# Haar_Primal_HardMount.net
KiCad netlist of a schematic drawn in EAGLE
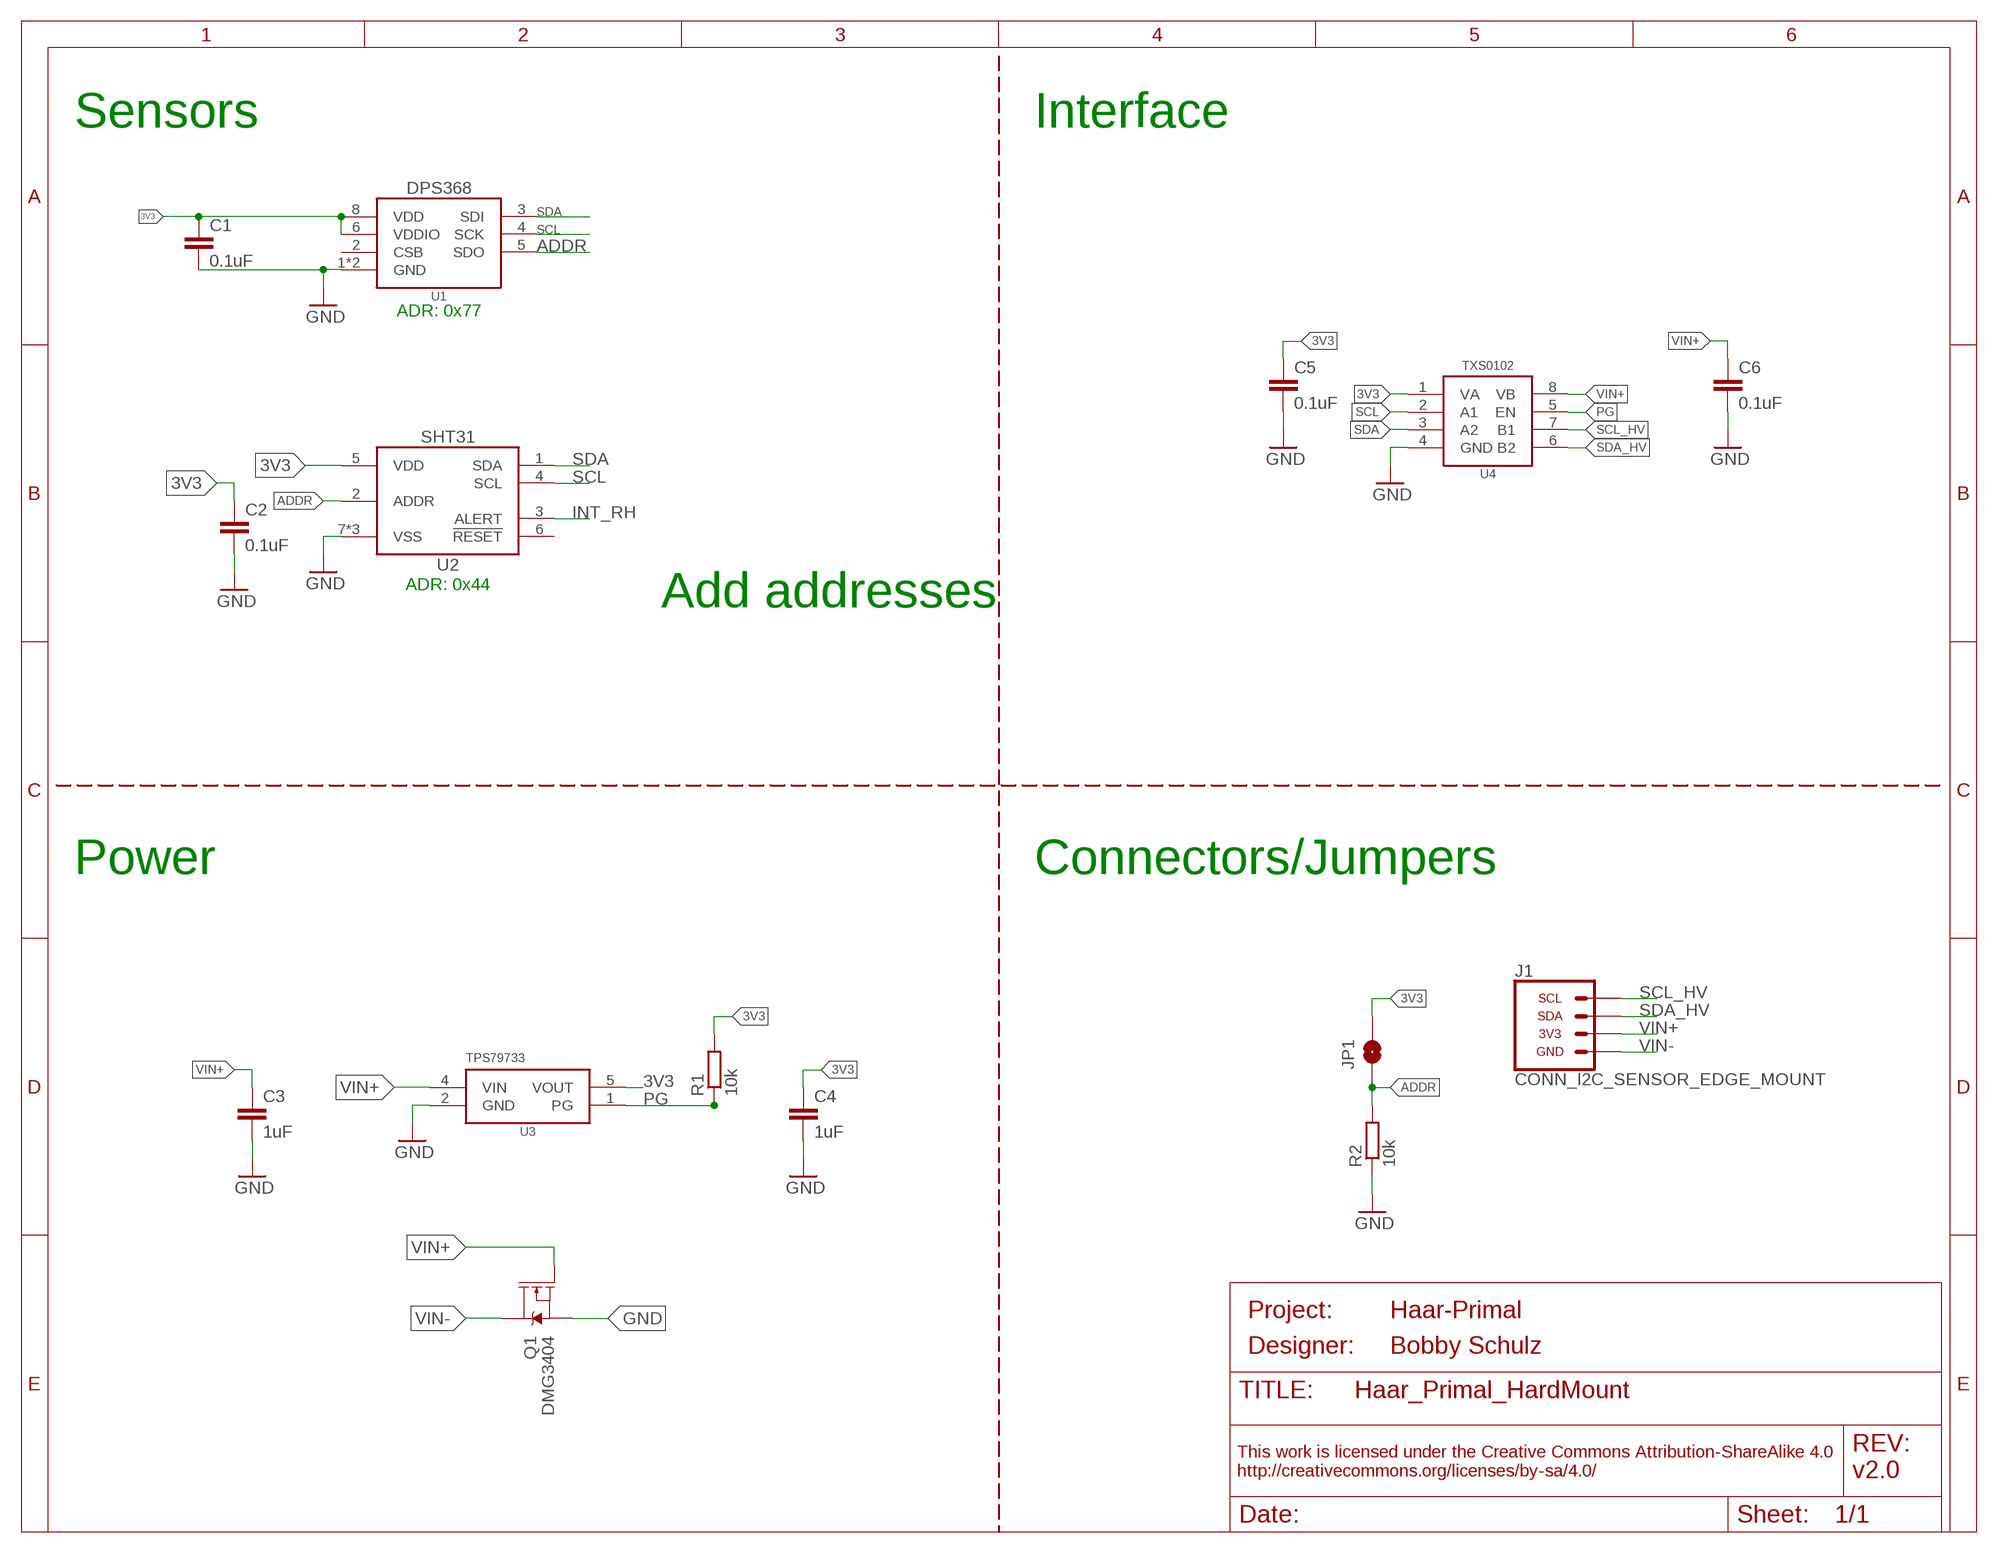
[diagram p0: schematic, sheet 1]

(export (version "E")
  (design (tool "Eeschema 10.0.6"))
  (components
    (comp (ref "C1")
      (value "0.1uF")
      (footprint "eagle-import:C0603")
      (fields (field (name "MF") "Murata") (field (name "MPN") "GCM188R71E104KA57D"))
      (libsource (lib "eagle-import") (part "C-EUC06030.1UF"))
    )
    (comp (ref "C2")
      (value "0.1uF")
      (footprint "eagle-import:C0603")
      (fields (field (name "MF") "Murata") (field (name "MPN") "GCM188R71E104KA57D"))
      (libsource (lib "eagle-import") (part "C-EUC06030.1UF"))
    )
    (comp (ref "C3")
      (value "1uF")
      (footprint "eagle-import:C0603")
      (fields (field (name "MF") "Yaiyo Yuden") (field (name "MPN") "EMK107BJ105KA-T"))
      (libsource (lib "eagle-import") (part "C-EUC06031UF"))
    )
    (comp (ref "C4")
      (value "1uF")
      (footprint "eagle-import:C0603")
      (fields (field (name "MF") "Yaiyo Yuden") (field (name "MPN") "EMK107BJ105KA-T"))
      (libsource (lib "eagle-import") (part "C-EUC06031UF"))
    )
    (comp (ref "C5")
      (value "0.1uF")
      (footprint "eagle-import:C0603")
      (fields (field (name "MF") "Murata") (field (name "MPN") "GCM188R71E104KA57D"))
      (libsource (lib "eagle-import") (part "C-EUC06030.1UF"))
    )
    (comp (ref "C6")
      (value "0.1uF")
      (footprint "eagle-import:C0603")
      (fields (field (name "MF") "Murata") (field (name "MPN") "GCM188R71E104KA57D"))
      (libsource (lib "eagle-import") (part "C-EUC06030.1UF"))
    )
    (comp (ref "J1")
      (value "CONN_I2C_SENSOR_EDGE_MOUNT")
      (footprint "eagle-import:SOLDERCUP_CONN_QUAD")
      (fields (field (name "MF") "TE Connectivity") (field (name "MPN") "1838893-2"))
      (libsource (lib "eagle-import") (part "CONN_I2C_SENSOR_EDGE_MOUNT"))
    )
    (comp (ref "JP1")
      (value "JUMPER-SMT_2_NO_SILK")
      (footprint "eagle-import:SMT-JUMPER_2_NO_SILK")
      (libsource (lib "eagle-import") (part "JUMPER-SMT_2_NO_SILK"))
    )
    (comp (ref "Q1")
      (value "DMG3404")
      (footprint "eagle-import:SOT23-3")
      (fields (field (name "MF") "Diodes Incorporated") (field (name "MPN") "DMG3404L-7"))
      (libsource (lib "eagle-import") (part "MOSFET-NCH-DMG3404L"))
    )
    (comp (ref "R1")
      (value "10k")
      (footprint "eagle-import:R0603")
      (fields (field (name "MF") "Yageo") (field (name "MPN") "RC0603FR-0710KL"))
      (libsource (lib "eagle-import") (part "R-EU_R060310K"))
    )
    (comp (ref "R2")
      (value "10k")
      (footprint "eagle-import:R0603")
      (fields (field (name "MF") "Yageo") (field (name "MPN") "RC0603FR-0710KL"))
      (libsource (lib "eagle-import") (part "R-EU_R060310K"))
    )
    (comp (ref "U1")
      (value "DPS368")
      (footprint "eagle-import:PG-VLGA-8")
      (fields
        (field (name "DISP") "DPS368")
        (field (name "MF") "Infineon")
        (field (name "MPN") "DPS368XTSA1")
      )
      (libsource (lib "eagle-import") (part "DPS368"))
    )
    (comp (ref "U2")
      (value "SHT31DFN")
      (footprint "eagle-import:DFN_8_2.5X2.5")
      (fields
        (field (name "DISP") "SHT31")
        (field (name "MF") "Sensirion")
        (field (name "MPN") "SHT31-DIS-F2.5KS")
      )
      (libsource (lib "eagle-import") (part "SHT3DFN1"))
    )
    (comp (ref "U3")
      (value "TPS79733")
      (footprint "eagle-import:DCK_R-PDSO-G5")
      (fields (field (name "DISP") "TPS79733") (field (name "MF") "TI") (field (name "MPN") "TPS79733DCKR"))
      (libsource (lib "eagle-import") (part "TPS79733"))
    )
    (comp (ref "U4")
      (value "TXS0102DQM")
      (footprint "eagle-import:DQM_R-PX2SON-N8")
      (fields (field (name "MF") "TI") (field (name "MPN") "TXS0102DQMR"))
      (libsource (lib "eagle-import") (part "TXS0102DQM"))
    )
  )
  (nets
    (net (code "1") (name "/INT_RH") (class "Default")
      (node (ref "U2") (pin "3") (pinfunction "ALERT_3") (pintype "output"))
    )
    (net (code "2") (name "3V3") (class "Default")
      (node (ref "C1") (pin "1") (pinfunction "1_1") (pintype "passive"))
      (node (ref "C2") (pin "1") (pinfunction "1_1") (pintype "passive"))
      (node (ref "C4") (pin "1") (pinfunction "1_1") (pintype "passive"))
      (node (ref "C5") (pin "1") (pinfunction "1_1") (pintype "passive"))
      (node (ref "JP1") (pin "2") (pinfunction "2_2") (pintype "passive"))
      (node (ref "R1") (pin "2") (pinfunction "2_2") (pintype "passive"))
      (node (ref "U1") (pin "6") (pinfunction "VDDIO_6") (pintype "bidirectional"))
      (node (ref "U1") (pin "8") (pinfunction "VDD_8") (pintype "power_in"))
      (node (ref "U2") (pin "5") (pinfunction "VDD_5") (pintype "power_in"))
      (node (ref "U3") (pin "5") (pinfunction "VOUT_5") (pintype "bidirectional"))
      (node (ref "U4") (pin "1") (pinfunction "VA_1") (pintype "power_in"))
    )
    (net (code "3") (name "ADDR") (class "Default")
      (node (ref "JP1") (pin "1") (pinfunction "1_1") (pintype "passive"))
      (node (ref "R2") (pin "2") (pinfunction "2_2") (pintype "passive"))
      (node (ref "U1") (pin "5") (pinfunction "SDO_5") (pintype "bidirectional"))
      (node (ref "U2") (pin "2") (pinfunction "ADDR_2") (pintype "input"))
    )
    (net (code "4") (name "GND") (class "Default")
      (node (ref "C1") (pin "2") (pinfunction "2_2") (pintype "passive"))
      (node (ref "C2") (pin "2") (pinfunction "2_2") (pintype "passive"))
      (node (ref "C3") (pin "2") (pinfunction "2_2") (pintype "passive"))
      (node (ref "C4") (pin "2") (pinfunction "2_2") (pintype "passive"))
      (node (ref "C5") (pin "2") (pinfunction "2_2") (pintype "passive"))
      (node (ref "C6") (pin "2") (pinfunction "2_2") (pintype "passive"))
      (node (ref "Q1") (pin "2") (pinfunction "S_2") (pintype "bidirectional"))
      (node (ref "R2") (pin "1") (pinfunction "1_1") (pintype "passive"))
      (node (ref "U1") (pin "1") (pinfunction "GND_1") (pintype "power_in"))
      (node (ref "U1") (pin "7") (pinfunction "GND_7") (pintype "power_in"))
      (node (ref "U2") (pin "7") (pinfunction "VSS_7") (pintype "power_in"))
      (node (ref "U2") (pin "8") (pinfunction "VSS_8") (pintype "power_in"))
      (node (ref "U2") (pin "EP") (pinfunction "VSS_EP") (pintype "power_in"))
      (node (ref "U3") (pin "2") (pinfunction "GND_2") (pintype "bidirectional"))
      (node (ref "U4") (pin "4") (pinfunction "GND_4") (pintype "power_in"))
    )
    (net (code "5") (name "PG") (class "Default")
      (node (ref "R1") (pin "1") (pinfunction "1_1") (pintype "passive"))
      (node (ref "U3") (pin "1") (pinfunction "PG_1") (pintype "bidirectional"))
      (node (ref "U4") (pin "5") (pinfunction "EN_5") (pintype "input"))
    )
    (net (code "6") (name "SCL") (class "Default")
      (node (ref "U1") (pin "4") (pinfunction "SCK_4") (pintype "bidirectional"))
      (node (ref "U2") (pin "4") (pinfunction "SCL_4") (pintype "input"))
      (node (ref "U4") (pin "2") (pinfunction "A1_2") (pintype "bidirectional"))
    )
    (net (code "7") (name "SCL_HV") (class "Default")
      (node (ref "J1") (pin "3") (pinfunction "SCL_3") (pintype "passive"))
      (node (ref "U4") (pin "7") (pinfunction "B1_7") (pintype "bidirectional"))
    )
    (net (code "8") (name "SDA") (class "Default")
      (node (ref "U1") (pin "3") (pinfunction "SDI_3") (pintype "bidirectional"))
      (node (ref "U2") (pin "1") (pinfunction "SDA_1") (pintype "bidirectional"))
      (node (ref "U4") (pin "3") (pinfunction "A2_3") (pintype "bidirectional"))
    )
    (net (code "9") (name "SDA_HV") (class "Default")
      (node (ref "J1") (pin "1") (pinfunction "SDA_1") (pintype "passive"))
      (node (ref "U4") (pin "6") (pinfunction "B2_6") (pintype "bidirectional"))
    )
    (net (code "10") (name "VIN+") (class "Default")
      (node (ref "C3") (pin "1") (pinfunction "1_1") (pintype "passive"))
      (node (ref "C6") (pin "1") (pinfunction "1_1") (pintype "passive"))
      (node (ref "J1") (pin "2") (pinfunction "3V3_2") (pintype "passive"))
      (node (ref "Q1") (pin "1") (pinfunction "G_1") (pintype "bidirectional"))
      (node (ref "U3") (pin "4") (pinfunction "VIN_4") (pintype "bidirectional"))
      (node (ref "U4") (pin "8") (pinfunction "VB_8") (pintype "power_in"))
    )
    (net (code "11") (name "VIN-") (class "Default")
      (node (ref "J1") (pin "4") (pinfunction "GND_4") (pintype "passive"))
      (node (ref "Q1") (pin "3") (pinfunction "D_3") (pintype "bidirectional"))
    )
    (net (code "12") (name "unconnected-(U1-CSB-Pad2)") (class "Default")
      (node (ref "U1") (pin "2") (pinfunction "CSB_2") (pintype "bidirectional"))
    )
    (net (code "13") (name "unconnected-(U2-~{RESET}-Pad6)") (class "Default")
      (node (ref "U2") (pin "6") (pinfunction "~{RESET}_6") (pintype "input"))
    )
  )
)
